# Hw_Sch.net
KiCad netlist of a schematic drawn in Altium Designer
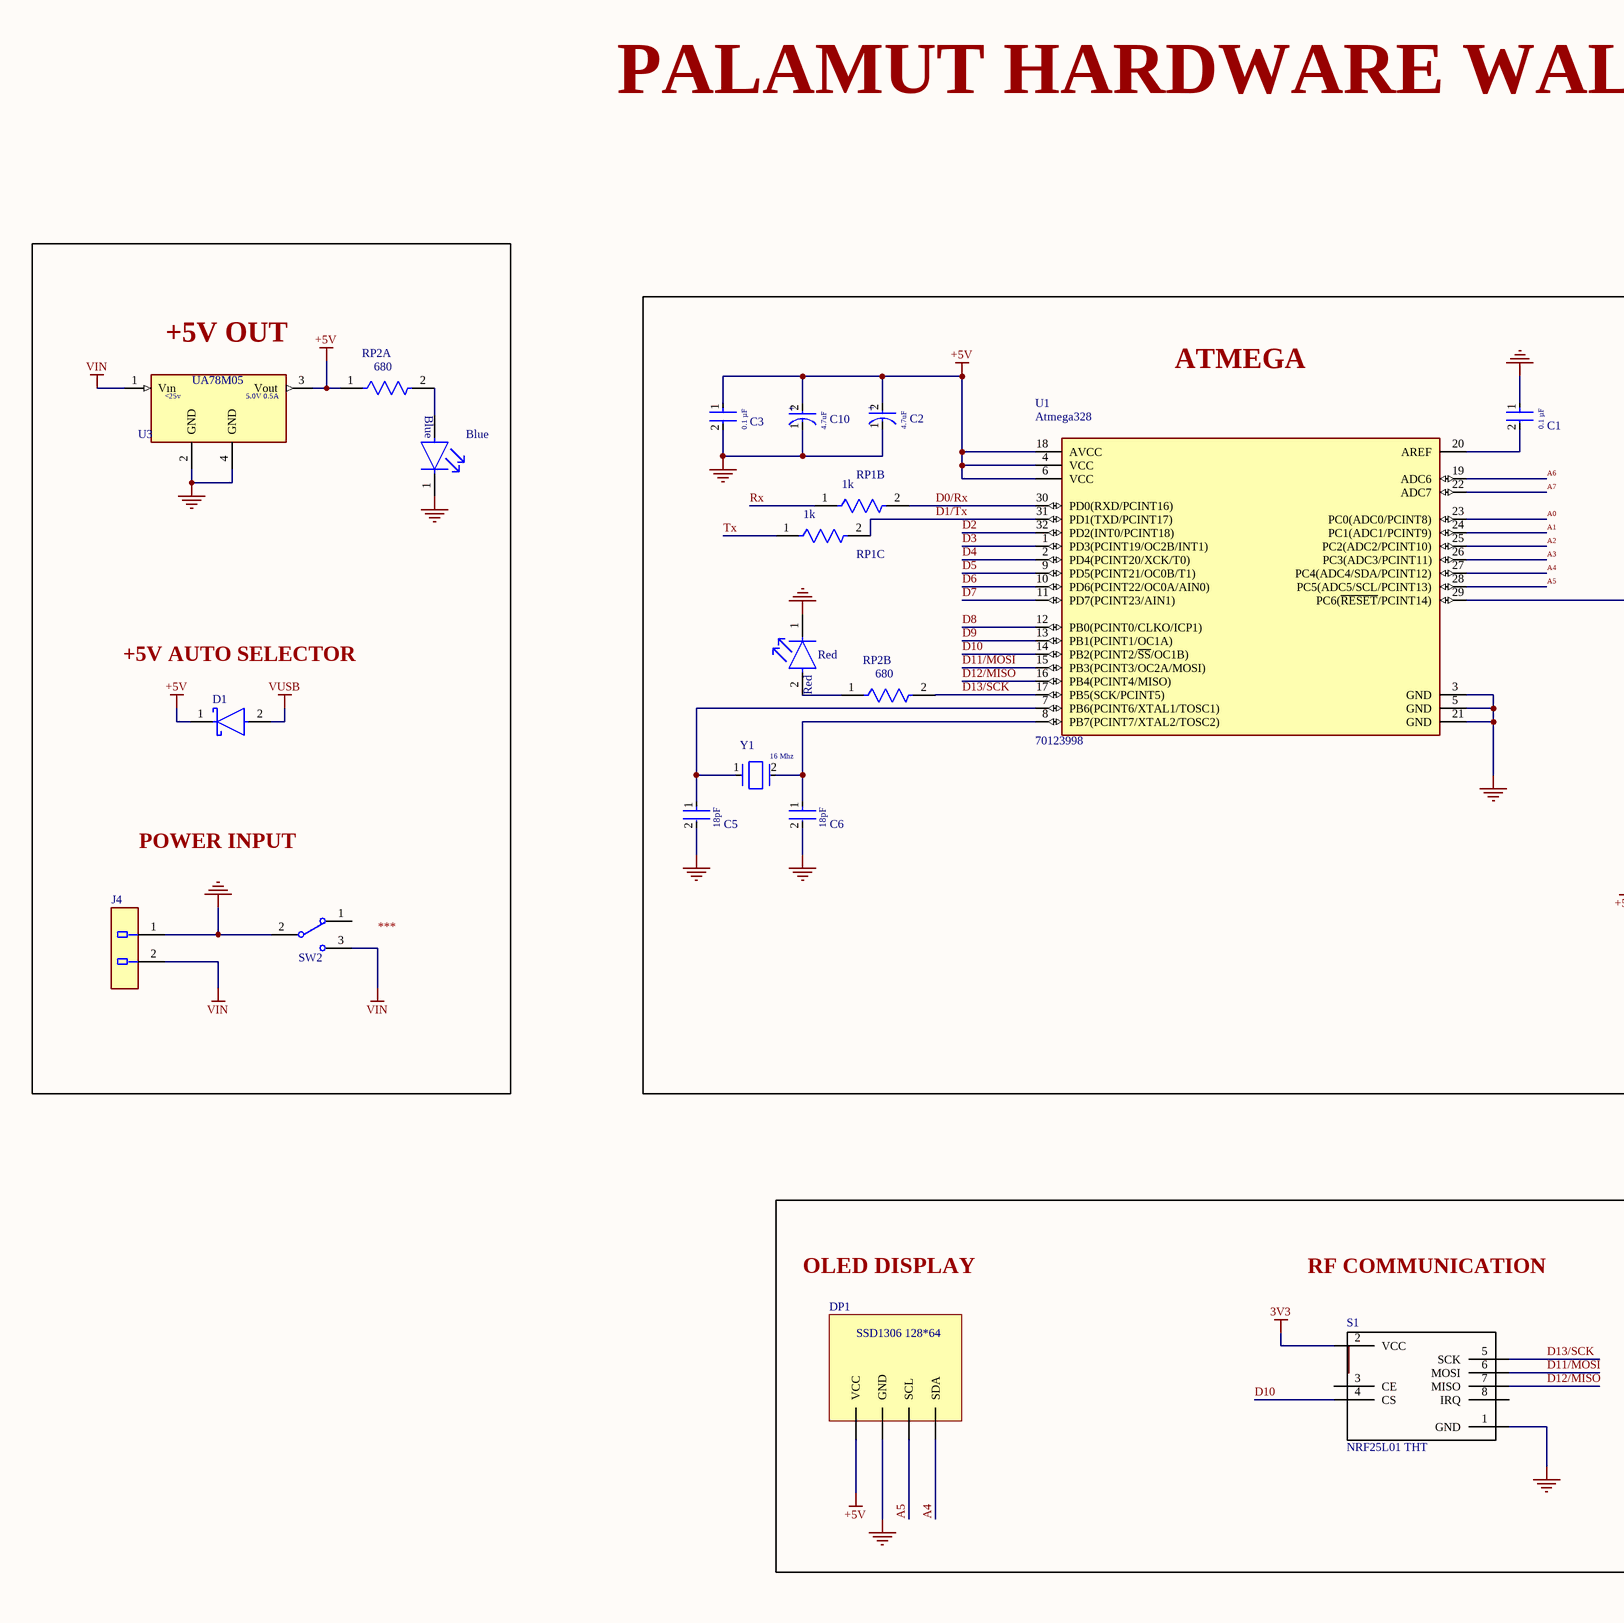
[diagram p0: Hw_Sch.SchDoc, left]
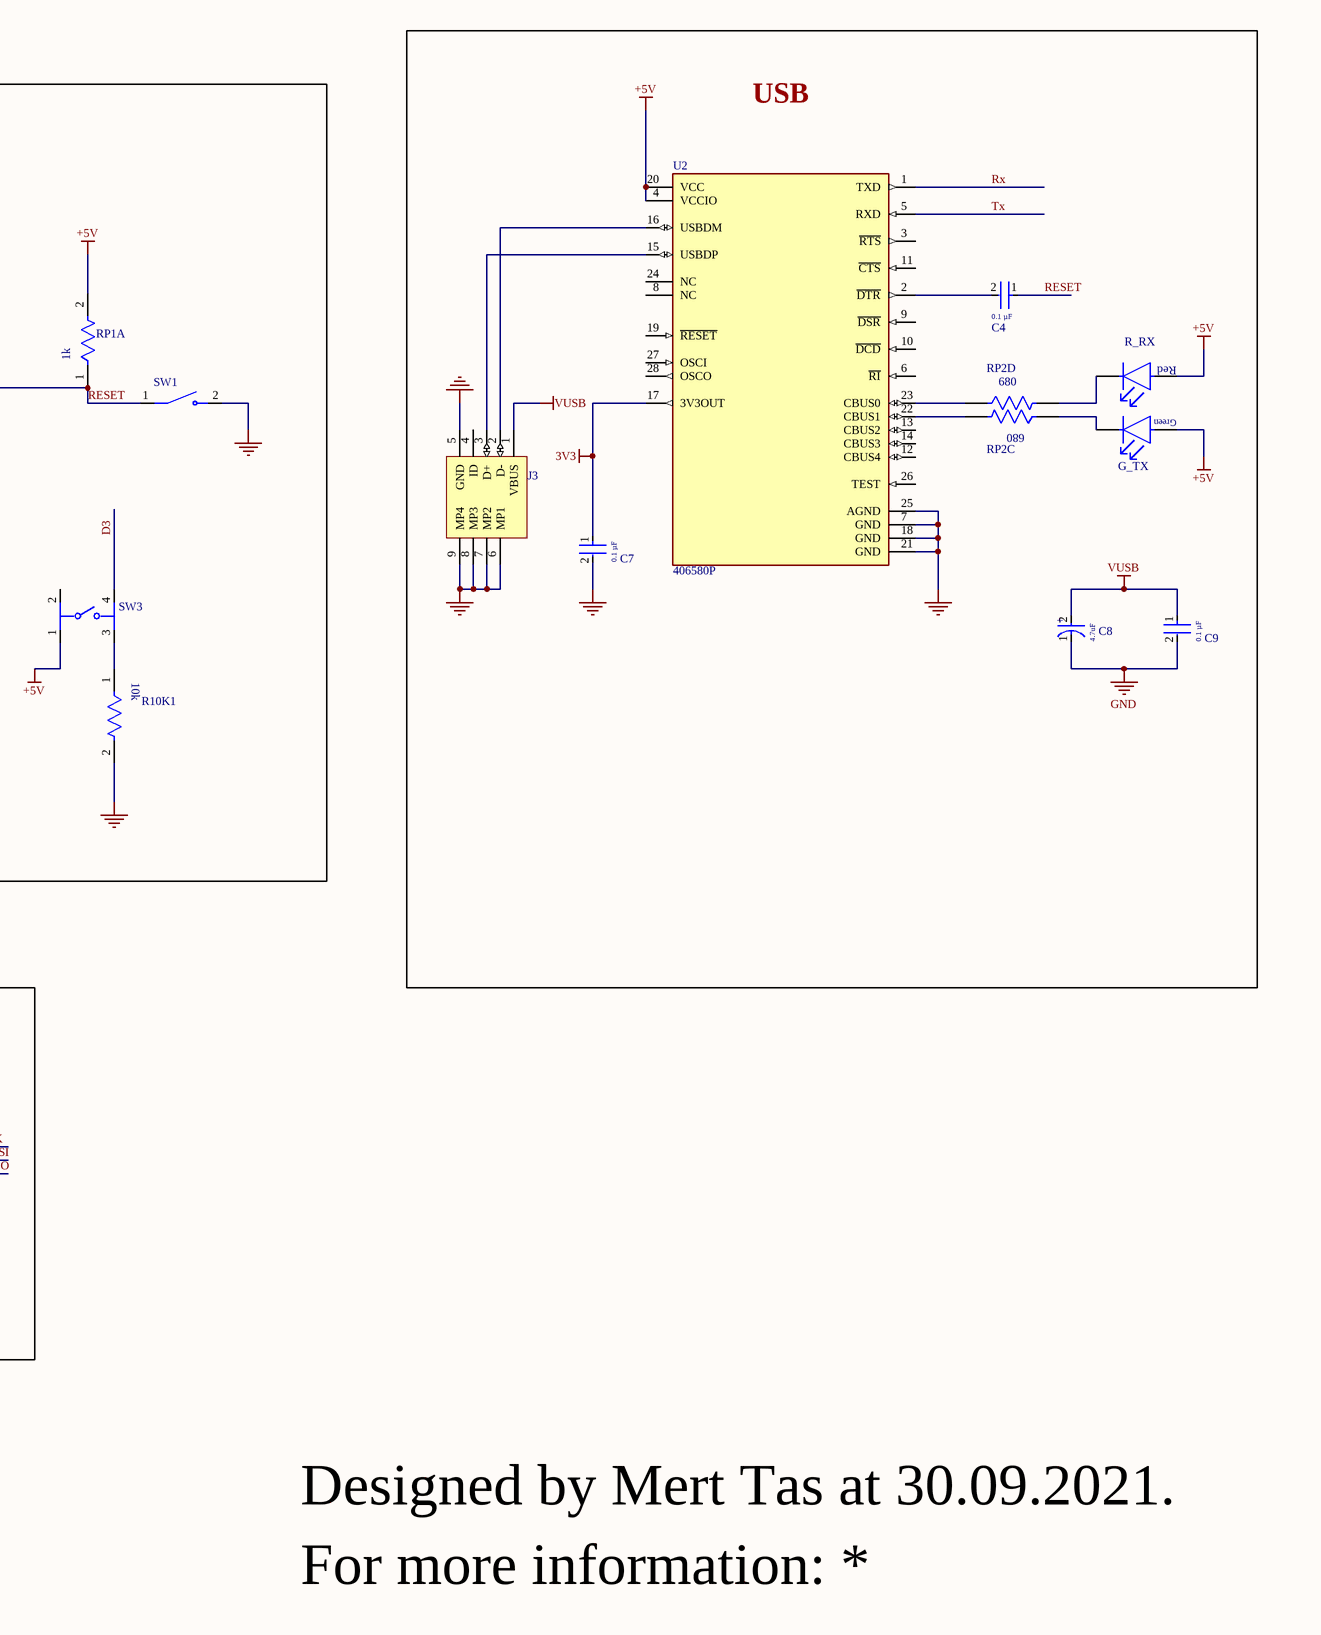
[diagram p1: Hw_Sch.SchDoc, right]

(export (version "E")
  (design (tool "Eeschema 10.0.6"))
  (components
    (comp (ref "Blue")
      (value "LTST-C170TBKT")
      (footprint "Lite-On_0_MFG")
      (libsource (lib "SCH_LED") (part "LTST-C170TBKT"))
    )
    (comp (ref "C1")
      (value "C0805C104K5RACTU")
      (footprint "KEMET_C0805C-DN_IPC_A")
      (libsource (lib "SCH_CAP") (part "C0805C104K5RACTU"))
    )
    (comp (ref "C2")
      (value "T491A475K010AT")
      (footprint "Kemet_T491A475K010AT_0")
      (libsource (lib "SCH_CAP") (part "T491A475K010AT"))
    )
    (comp (ref "C3")
      (value "C0805C104K5RACTU")
      (footprint "KEMET_C0805C-DN_IPC_A")
      (libsource (lib "SCH_CAP") (part "C0805C104K5RACTU"))
    )
    (comp (ref "C4")
      (value "C0805C104K5RACTU")
      (footprint "KEMET_C0805C-DN_IPC_A")
      (libsource (lib "SCH_CAP") (part "C0805C104K5RACTU"))
    )
    (comp (ref "C5")
      (value "C0805C180J5GACTU")
      (footprint "KEMET_C0805C-DN_IPC_A - duplicate")
      (libsource (lib "SCH_CAP") (part "C0805C180J5GACTU"))
    )
    (comp (ref "C6")
      (value "C0805C180J5GACTU")
      (footprint "KEMET_C0805C-DN_IPC_A - duplicate")
      (libsource (lib "SCH_CAP") (part "C0805C180J5GACTU"))
    )
    (comp (ref "C7")
      (value "C0805C104K5RACTU")
      (footprint "KEMET_C0805C-DN_IPC_A")
      (libsource (lib "SCH_CAP") (part "C0805C104K5RACTU"))
    )
    (comp (ref "C8")
      (value "T491A475K010AT")
      (footprint "Kemet_T491A475K010AT_0")
      (libsource (lib "SCH_CAP") (part "T491A475K010AT"))
    )
    (comp (ref "C9")
      (value "C0805C104K5RACTU")
      (footprint "KEMET_C0805C-DN_IPC_A")
      (libsource (lib "SCH_CAP") (part "C0805C104K5RACTU"))
    )
    (comp (ref "C10")
      (value "T491A475K010AT")
      (footprint "Kemet_T491A475K010AT_0")
      (libsource (lib "SCH_CAP") (part "T491A475K010AT"))
    )
    (comp (ref "D1")
      (value "MBR0520LT1G")
      (footprint "On_Semiconductor_425-04_IPC_A")
      (libsource (lib "SCH_DIOS") (part "MBR0520LT1G"))
    )
    (comp (ref "DP1")
      (value "SSD1306 0.96 inch")
      (footprint "SSD1306 128*64")
      (libsource (lib "SCH_LCD") (part "SSD1306 0.96 inch"))
    )
    (comp (ref "G_TX")
      (value "APHCM2012CGCK-F01")
      (footprint "Kingbright_0_MFG")
      (libsource (lib "SCH_LED") (part "APHCM2012CGCK-F01"))
    )
    (comp (ref "J3")
      (value "67503-1020")
      (footprint "MOLX-67503-1020_V")
      (description "USB, MINI, SMD, RA KME04-USBMU03A01")
      (fields (field (name "MANUFACTURER") "Molex"))
      (libsource (lib "SCH_CON") (part "67503-1020"))
    )
    (comp (ref "J4")
      (value "S2B-PH-K-S_LF_SN")
      (footprint "JST_S2B-PH-K-S_LF_SN_0")
      (libsource (lib "SCH_CON") (part "S2B-PH-K-S_LF_SN"))
    )
    (comp (ref "R10K1")
      (value "MCT0603MD1002DP500")
      (footprint "Vishay_MCT0603_IPC_A")
      (libsource (lib "SCH_RES") (part "MCT0603MD1002DP500"))
    )
    (comp (ref "Red")
      (value "APT2012SRCPRV")
      (footprint "Kingbright_APT2012SRCPRV_0")
      (libsource (lib "") (part "APT2012SRCPRV_1"))
    )
    (comp (ref "RP1A")
      (value "RC0603FR-071KL")
      (footprint "Yageo_RC0603_IPC_A - duplicate")
      (libsource (lib "SCH_RES") (part "RC0603FR-071KL"))
    )
    (comp (ref "RP1B")
      (value "RC0603FR-071KL")
      (footprint "Yageo_RC0603_IPC_A - duplicate")
      (libsource (lib "SCH_RES") (part "RC0603FR-071KL"))
    )
    (comp (ref "RP1C")
      (value "RC0603FR-071KL")
      (footprint "Yageo_RC0603_IPC_A - duplicate")
      (libsource (lib "SCH_RES") (part "RC0603FR-071KL"))
    )
    (comp (ref "RP2A")
      (value "RC0603FR-07680RL")
      (footprint "Yageo_RC0603_IPC_A")
      (libsource (lib "") (part "RC0603FR-07680RL_1"))
    )
    (comp (ref "RP2B")
      (value "RC0603FR-07680RL")
      (footprint "Yageo_RC0603_IPC_A")
      (libsource (lib "") (part "RC0603FR-07680RL_1"))
    )
    (comp (ref "RP2C")
      (value "RC0603FR-07680RL")
      (footprint "Yageo_RC0603_IPC_A")
      (libsource (lib "SCH_RES") (part "RC0603FR-07680RL"))
    )
    (comp (ref "RP2D")
      (value "RC0603FR-07680RL")
      (footprint "Yageo_RC0603_IPC_A")
      (libsource (lib "SCH_RES") (part "RC0603FR-07680RL"))
    )
    (comp (ref "R_RX")
      (value "APT2012SRCPRV")
      (footprint "Kingbright_APT2012SRCPRV_0")
      (libsource (lib "SCH_LED") (part "APT2012SRCPRV"))
    )
    (comp (ref "S1")
      (value "NRF25L01 THT")
      (footprint "NRF25L01 THT")
      (libsource (lib "SCH_RF") (part "NRF25L01 THT"))
    )
    (comp (ref "SW1")
      (value "B3U-1000P")
      (footprint "Omron_0_MFG")
      (description "Tactile Switch SPST-NO Top Actuated Surface Mount")
      (fields (field (name "MF") "Omron") (field (name "DIGI-KEY_PART_NUMBER") "SW1020CT-ND"))
      (libsource (lib "SCH_SW") (part "B3U-1000P"))
    )
    (comp (ref "SW2")
      (value "EG1218")
      (footprint "ESWI-EG1218_V")
      (description "Slide Switch, 500 V, -20 to 70 degC, 3-Pin THD, RoHS")
      (libsource (lib "SCH_SW") (part "EG1218"))
    )
    (comp (ref "SW3")
      (value "B3SL-1002P")
      (footprint "Omron_B3SL-1022P_0")
      (libsource (lib "SCH_SW") (part "B3SL-1002P"))
    )
    (comp (ref "U1")
      (value "ATMEGA168-20AU")
      (footprint "Microchip_32A_IPC_A")
      (fields (field (name "SUPPLIER PART NUMBER 1") "70123998"))
      (libsource (lib "SCH_IC") (part "ATMEGA168-20AU"))
    )
    (comp (ref "U2")
      (value "FT232RL-REEL")
      (footprint "FTDI_SSOP-28_IPC_A")
      (fields (field (name "SUPPLIER PART NUMBER 1") "406580P"))
      (libsource (lib "SCH_IC") (part "FT232RL-REEL"))
    )
    (comp (ref "U3")
      (value "UA78M05CDCYR")
      (footprint "Texas_Instruments_DCY0004A_IPC_A")
      (libsource (lib "SCH_IC") (part "UA78M05CDCYR"))
    )
    (comp (ref "Y1")
      (value "Crys_CTS_ATS16B_eec")
      (footprint "CTS_ATS16B_0")
      (description "CRYSTAL 16.0000MHZ 18PF T/H")
      (fields (field (name "PART NUMBER") "ATS16B") (field (name "MANUFACTURER") "CTS"))
      (libsource (lib "SCH_CRYSTAL") (part "Crys_CTS_ATS16B_eec"))
    )
  )
  (nets
    (net (code "1") (name "+5V") (class "Default")
      (node (ref "C10") (pin "2") (pinfunction "A_2") (pintype "passive"))
      (node (ref "C2") (pin "2") (pinfunction "A_2") (pintype "passive"))
      (node (ref "C3") (pin "1") (pinfunction "1_1") (pintype "passive"))
      (node (ref "D1") (pin "1") (pinfunction "C_1") (pintype "passive"))
      (node (ref "DP1") (pin "1") (pinfunction "VCC_1") (pintype "passive"))
      (node (ref "G_TX") (pin "2") (pinfunction "A_2") (pintype "passive"))
      (node (ref "RP1A") (pin "2") (pinfunction "2_2") (pintype "passive"))
      (node (ref "RP2A") (pin "1") (pinfunction "1_1") (pintype "passive"))
      (node (ref "R_RX") (pin "2") (pinfunction "A_2") (pintype "passive"))
      (node (ref "SW3") (pin "1") (pinfunction "1_1") (pintype "passive"))
      (node (ref "U1") (pin "18") (pinfunction "AVCC_18") (pintype "power_in"))
      (node (ref "U1") (pin "4") (pinfunction "VCC_4") (pintype "power_in"))
      (node (ref "U1") (pin "6") (pinfunction "VCC_6") (pintype "power_in"))
      (node (ref "U2") (pin "20") (pinfunction "VCC_20") (pintype "power_in"))
      (node (ref "U2") (pin "4") (pinfunction "VCCIO_4") (pintype "power_in"))
      (node (ref "U3") (pin "3") (pinfunction "Vout_3") (pintype "output"))
    )
    (net (code "2") (name "/A0") (class "Default")
      (node (ref "U1") (pin "23") (pinfunction "PC0(ADC0/PCINT8)_23") (pintype "bidirectional"))
    )
    (net (code "3") (name "/A1") (class "Default")
      (node (ref "U1") (pin "24") (pinfunction "PC1(ADC1/PCINT9)_24") (pintype "bidirectional"))
    )
    (net (code "4") (name "/A2") (class "Default")
      (node (ref "U1") (pin "25") (pinfunction "PC2(ADC2/PCINT10)_25") (pintype "bidirectional"))
    )
    (net (code "5") (name "/A3") (class "Default")
      (node (ref "U1") (pin "26") (pinfunction "PC3(ADC3/PCINT11)_26") (pintype "bidirectional"))
    )
    (net (code "6") (name "/A4") (class "Default")
      (node (ref "DP1") (pin "4") (pinfunction "SDA_4") (pintype "passive"))
      (node (ref "U1") (pin "27") (pinfunction "PC4(ADC4/SDA/PCINT12)_27") (pintype "bidirectional"))
    )
    (net (code "7") (name "/A5") (class "Default")
      (node (ref "DP1") (pin "3") (pinfunction "SCL_3") (pintype "passive"))
      (node (ref "U1") (pin "28") (pinfunction "PC5(ADC5/SCL/PCINT13)_28") (pintype "bidirectional"))
    )
    (net (code "8") (name "/A6") (class "Default")
      (node (ref "U1") (pin "19") (pinfunction "ADC6_19") (pintype "bidirectional"))
    )
    (net (code "9") (name "/A7") (class "Default")
      (node (ref "U1") (pin "22") (pinfunction "ADC7_22") (pintype "bidirectional"))
    )
    (net (code "10") (name "/D0{slash}Rx") (class "Default")
      (node (ref "RP1B") (pin "2") (pinfunction "2_2") (pintype "passive"))
      (node (ref "U1") (pin "30") (pinfunction "PD0(RXD/PCINT16)_30") (pintype "bidirectional"))
    )
    (net (code "11") (name "/D1{slash}Tx") (class "Default")
      (node (ref "RP1C") (pin "2") (pinfunction "2_2") (pintype "passive"))
      (node (ref "U1") (pin "31") (pinfunction "PD1(TXD/PCINT17)_31") (pintype "bidirectional"))
    )
    (net (code "12") (name "/D2") (class "Default")
      (node (ref "U1") (pin "32") (pinfunction "PD2(INT0/PCINT18)_32") (pintype "bidirectional"))
    )
    (net (code "13") (name "/D3") (class "Default")
      (node (ref "SW3") (pin "4") (pinfunction "4_4") (pintype "passive"))
      (node (ref "U1") (pin "1") (pinfunction "PD3(PCINT19/OC2B/INT1)_1") (pintype "bidirectional"))
    )
    (net (code "14") (name "/D4") (class "Default")
      (node (ref "U1") (pin "2") (pinfunction "PD4(PCINT20/XCK/T0)_2") (pintype "bidirectional"))
    )
    (net (code "15") (name "/D5") (class "Default")
      (node (ref "U1") (pin "9") (pinfunction "PD5(PCINT21/OC0B/T1)_9") (pintype "bidirectional"))
    )
    (net (code "16") (name "/D6") (class "Default")
      (node (ref "U1") (pin "10") (pinfunction "PD6(PCINT22/OC0A/AIN0)_10") (pintype "bidirectional"))
    )
    (net (code "17") (name "/D7") (class "Default")
      (node (ref "U1") (pin "11") (pinfunction "PD7(PCINT23/AIN1)_11") (pintype "bidirectional"))
    )
    (net (code "18") (name "/D8") (class "Default")
      (node (ref "U1") (pin "12") (pinfunction "PB0(PCINT0/CLKO/ICP1)_12") (pintype "bidirectional"))
    )
    (net (code "19") (name "/D9") (class "Default")
      (node (ref "U1") (pin "13") (pinfunction "PB1(PCINT1/OC1A)_13") (pintype "bidirectional"))
    )
    (net (code "20") (name "/D10") (class "Default")
      (node (ref "S1") (pin "4") (pinfunction "CS_4") (pintype "passive"))
      (node (ref "U1") (pin "14") (pinfunction "PB2(PCINT2/~{SS}/OC1B)_14") (pintype "bidirectional"))
    )
    (net (code "21") (name "/D11{slash}MOSI") (class "Default")
      (node (ref "S1") (pin "6") (pinfunction "MOSI_6") (pintype "passive"))
      (node (ref "U1") (pin "15") (pinfunction "PB3(PCINT3/OC2A/MOSI)_15") (pintype "bidirectional"))
    )
    (net (code "22") (name "/D12{slash}MISO") (class "Default")
      (node (ref "S1") (pin "7") (pinfunction "MISO_7") (pintype "passive"))
      (node (ref "U1") (pin "16") (pinfunction "PB4(PCINT4/MISO)_16") (pintype "bidirectional"))
    )
    (net (code "23") (name "/D13{slash}SCK") (class "Default")
      (node (ref "RP2B") (pin "2") (pinfunction "2_2") (pintype "passive"))
      (node (ref "S1") (pin "5") (pinfunction "SCK_5") (pintype "passive"))
      (node (ref "U1") (pin "17") (pinfunction "PB5(SCK/PCINT5)_17") (pintype "bidirectional"))
    )
    (net (code "24") (name "/RESET") (class "Default")
      (node (ref "C4") (pin "1") (pinfunction "1_1") (pintype "passive"))
      (node (ref "RP1A") (pin "1") (pinfunction "1_1") (pintype "passive"))
      (node (ref "SW1") (pin "1") (pinfunction "1_1") (pintype "passive"))
      (node (ref "U1") (pin "29") (pinfunction "PC6(~{RESET}/PCINT14)_29") (pintype "bidirectional"))
    )
    (net (code "25") (name "/Rx") (class "Default")
      (node (ref "RP1B") (pin "1") (pinfunction "1_1") (pintype "passive"))
      (node (ref "U2") (pin "1") (pinfunction "TXD_1") (pintype "output"))
    )
    (net (code "26") (name "/Tx") (class "Default")
      (node (ref "RP1C") (pin "1") (pinfunction "1_1") (pintype "passive"))
      (node (ref "U2") (pin "5") (pinfunction "RXD_5") (pintype "input"))
    )
    (net (code "27") (name "3V3") (class "Default")
      (node (ref "C7") (pin "1") (pinfunction "1_1") (pintype "passive"))
      (node (ref "S1") (pin "2") (pinfunction "VCC_2") (pintype "power_in"))
      (node (ref "U2") (pin "17") (pinfunction "3V3OUT_17") (pintype "output"))
    )
    (net (code "28") (name "GND") (class "Default")
      (node (ref "Blue") (pin "1") (pinfunction "C_1") (pintype "passive"))
      (node (ref "C1") (pin "1") (pinfunction "1_1") (pintype "passive"))
      (node (ref "C10") (pin "1") (pinfunction "C_1") (pintype "passive"))
      (node (ref "C2") (pin "1") (pinfunction "C_1") (pintype "passive"))
      (node (ref "C3") (pin "2") (pinfunction "2_2") (pintype "passive"))
      (node (ref "C5") (pin "2") (pinfunction "2_2") (pintype "passive"))
      (node (ref "C6") (pin "2") (pinfunction "2_2") (pintype "passive"))
      (node (ref "C7") (pin "2") (pinfunction "2_2") (pintype "passive"))
      (node (ref "C8") (pin "1") (pinfunction "C_1") (pintype "passive"))
      (node (ref "C9") (pin "2") (pinfunction "2_2") (pintype "passive"))
      (node (ref "DP1") (pin "2") (pinfunction "GND_2") (pintype "passive"))
      (node (ref "J3") (pin "5") (pinfunction "GND_5") (pintype "power_in"))
      (node (ref "J3") (pin "6") (pinfunction "MP1_6") (pintype "passive"))
      (node (ref "J3") (pin "7") (pinfunction "MP2_7") (pintype "passive"))
      (node (ref "J3") (pin "8") (pinfunction "MP3_8") (pintype "passive"))
      (node (ref "J3") (pin "9") (pinfunction "MP4_9") (pintype "passive"))
      (node (ref "J4") (pin "1") (pinfunction "1_1") (pintype "passive"))
      (node (ref "R10K1") (pin "2") (pinfunction "2_2") (pintype "passive"))
      (node (ref "Red") (pin "1") (pinfunction "C_1") (pintype "passive"))
      (node (ref "S1") (pin "1") (pinfunction "GND_1") (pintype "power_in"))
      (node (ref "SW1") (pin "2") (pinfunction "2_2") (pintype "passive"))
      (node (ref "SW2") (pin "2") (pinfunction "COM_2") (pintype "passive"))
      (node (ref "U1") (pin "21") (pinfunction "GND_21") (pintype "power_in"))
      (node (ref "U1") (pin "3") (pinfunction "GND_3") (pintype "power_in"))
      (node (ref "U1") (pin "5") (pinfunction "GND_5") (pintype "power_in"))
      (node (ref "U2") (pin "18") (pinfunction "GND_18") (pintype "power_in"))
      (node (ref "U2") (pin "21") (pinfunction "GND_21") (pintype "power_in"))
      (node (ref "U2") (pin "25") (pinfunction "AGND_25") (pintype "power_in"))
      (node (ref "U2") (pin "7") (pinfunction "GND_7") (pintype "power_in"))
      (node (ref "U3") (pin "2") (pinfunction "GND_2") (pintype "power_in"))
      (node (ref "U3") (pin "4") (pinfunction "GND_4") (pintype "power_in"))
    )
    (net (code "29") (name "Net-(Blue-A)") (class "Default")
      (node (ref "Blue") (pin "2") (pinfunction "A_2") (pintype "passive"))
      (node (ref "RP2A") (pin "2") (pinfunction "2_2") (pintype "passive"))
    )
    (net (code "30") (name "Net-(G_TX-C)") (class "Default")
      (node (ref "G_TX") (pin "1") (pinfunction "C_1") (pintype "passive"))
      (node (ref "RP2C") (pin "1") (pinfunction "1_1") (pintype "passive"))
    )
    (net (code "31") (name "Net-(J3-D+)") (class "Default")
      (node (ref "J3") (pin "3") (pinfunction "D+_3") (pintype "bidirectional"))
      (node (ref "U2") (pin "15") (pinfunction "USBDP_15") (pintype "bidirectional"))
    )
    (net (code "32") (name "Net-(J3-D-)") (class "Default")
      (node (ref "J3") (pin "2") (pinfunction "D-_2") (pintype "bidirectional"))
      (node (ref "U2") (pin "16") (pinfunction "USBDM_16") (pintype "bidirectional"))
    )
    (net (code "33") (name "Net-(R10K1-Pad1)") (class "Default")
      (node (ref "R10K1") (pin "1") (pinfunction "1_1") (pintype "passive"))
      (node (ref "SW3") (pin "3") (pinfunction "3_3") (pintype "passive"))
    )
    (net (code "34") (name "Net-(R_RX-C)") (class "Default")
      (node (ref "RP2D") (pin "2") (pinfunction "2_2") (pintype "passive"))
      (node (ref "R_RX") (pin "1") (pinfunction "C_1") (pintype "passive"))
    )
    (net (code "35") (name "Net-(Red-A)") (class "Default")
      (node (ref "RP2B") (pin "1") (pinfunction "1_1") (pintype "passive"))
      (node (ref "Red") (pin "2") (pinfunction "A_2") (pintype "passive"))
    )
    (net (code "36") (name "Net-(U1-AREF)") (class "Default")
      (node (ref "C1") (pin "2") (pinfunction "2_2") (pintype "passive"))
      (node (ref "U1") (pin "20") (pinfunction "AREF_20") (pintype "passive"))
    )
    (net (code "37") (name "Net-(U1-PB6(PCINT6{slash}XTAL1{slash}TOSC1))") (class "Default")
      (node (ref "C5") (pin "1") (pinfunction "1_1") (pintype "passive"))
      (node (ref "U1") (pin "7") (pinfunction "PB6(PCINT6/XTAL1/TOSC1)_7") (pintype "bidirectional"))
      (node (ref "Y1") (pin "1") (pinfunction "1_1") (pintype "passive"))
    )
    (net (code "38") (name "Net-(U1-PB7(PCINT7{slash}XTAL2{slash}TOSC2))") (class "Default")
      (node (ref "C6") (pin "1") (pinfunction "1_1") (pintype "passive"))
      (node (ref "U1") (pin "8") (pinfunction "PB7(PCINT7/XTAL2/TOSC2)_8") (pintype "bidirectional"))
      (node (ref "Y1") (pin "2") (pinfunction "2_2") (pintype "passive"))
    )
    (net (code "39") (name "Net-(U2-CBUS0)") (class "Default")
      (node (ref "RP2D") (pin "1") (pinfunction "1_1") (pintype "passive"))
      (node (ref "U2") (pin "23") (pinfunction "CBUS0_23") (pintype "bidirectional"))
    )
    (net (code "40") (name "Net-(U2-CBUS1)") (class "Default")
      (node (ref "RP2C") (pin "2") (pinfunction "2_2") (pintype "passive"))
      (node (ref "U2") (pin "22") (pinfunction "CBUS1_22") (pintype "bidirectional"))
    )
    (net (code "41") (name "Net-(U2-~{DTR})") (class "Default")
      (node (ref "C4") (pin "2") (pinfunction "2_2") (pintype "passive"))
      (node (ref "U2") (pin "2") (pinfunction "~{DTR}_2") (pintype "output"))
    )
    (net (code "42") (name "VIN") (class "Default")
      (node (ref "J4") (pin "2") (pinfunction "2_2") (pintype "passive"))
      (node (ref "SW2") (pin "3") (pinfunction "3_3") (pintype "passive"))
      (node (ref "U3") (pin "1") (pinfunction "Vın_1") (pintype "input"))
    )
    (net (code "43") (name "VUSB") (class "Default")
      (node (ref "C8") (pin "2") (pinfunction "A_2") (pintype "passive"))
      (node (ref "C9") (pin "1") (pinfunction "1_1") (pintype "passive"))
      (node (ref "D1") (pin "2") (pinfunction "A_2") (pintype "passive"))
      (node (ref "J3") (pin "1") (pinfunction "VBUS_1") (pintype "power_in"))
    )
    (net (code "44") (name "unconnected-(J3-ID-Pad4)") (class "Default")
      (node (ref "J3") (pin "4") (pinfunction "ID_4") (pintype "passive"))
    )
    (net (code "45") (name "unconnected-(S1-CE-Pad3)") (class "Default")
      (node (ref "S1") (pin "3") (pinfunction "CE_3") (pintype "passive"))
    )
    (net (code "46") (name "unconnected-(S1-IRQ-Pad8)") (class "Default")
      (node (ref "S1") (pin "8") (pinfunction "IRQ_8") (pintype "passive"))
    )
    (net (code "47") (name "unconnected-(SW2-Pad1)") (class "Default")
      (node (ref "SW2") (pin "1") (pinfunction "1_1") (pintype "passive"))
    )
    (net (code "48") (name "unconnected-(SW3-Pad2)") (class "Default")
      (node (ref "SW3") (pin "2") (pinfunction "2_2") (pintype "passive"))
    )
    (net (code "49") (name "unconnected-(U2-CBUS2-Pad13)") (class "Default")
      (node (ref "U2") (pin "13") (pinfunction "CBUS2_13") (pintype "bidirectional"))
    )
    (net (code "50") (name "unconnected-(U2-CBUS3-Pad14)") (class "Default")
      (node (ref "U2") (pin "14") (pinfunction "CBUS3_14") (pintype "bidirectional"))
    )
    (net (code "51") (name "unconnected-(U2-CBUS4-Pad12)") (class "Default")
      (node (ref "U2") (pin "12") (pinfunction "CBUS4_12") (pintype "bidirectional"))
    )
    (net (code "52") (name "unconnected-(U2-NC-Pad8)") (class "Default")
      (node (ref "U2") (pin "8") (pinfunction "NC_8") (pintype "passive"))
    )
    (net (code "53") (name "unconnected-(U2-NC-Pad24)") (class "Default")
      (node (ref "U2") (pin "24") (pinfunction "NC_24") (pintype "passive"))
    )
    (net (code "54") (name "unconnected-(U2-OSCI-Pad27)") (class "Default")
      (node (ref "U2") (pin "27") (pinfunction "OSCI_27") (pintype "input"))
    )
    (net (code "55") (name "unconnected-(U2-OSCO-Pad28)") (class "Default")
      (node (ref "U2") (pin "28") (pinfunction "OSCO_28") (pintype "output"))
    )
    (net (code "56") (name "unconnected-(U2-TEST-Pad26)") (class "Default")
      (node (ref "U2") (pin "26") (pinfunction "TEST_26") (pintype "input"))
    )
    (net (code "57") (name "unconnected-(U2-~{CTS}-Pad11)") (class "Default")
      (node (ref "U2") (pin "11") (pinfunction "~{CTS}_11") (pintype "input"))
    )
    (net (code "58") (name "unconnected-(U2-~{DCD}-Pad10)") (class "Default")
      (node (ref "U2") (pin "10") (pinfunction "~{DCD}_10") (pintype "input"))
    )
    (net (code "59") (name "unconnected-(U2-~{DSR}-Pad9)") (class "Default")
      (node (ref "U2") (pin "9") (pinfunction "~{DSR}_9") (pintype "input"))
    )
    (net (code "60") (name "unconnected-(U2-~{RESET}-Pad19)") (class "Default")
      (node (ref "U2") (pin "19") (pinfunction "~{RESET}_19") (pintype "input"))
    )
    (net (code "61") (name "unconnected-(U2-~{RI}-Pad6)") (class "Default")
      (node (ref "U2") (pin "6") (pinfunction "~{RI}_6") (pintype "input"))
    )
    (net (code "62") (name "unconnected-(U2-~{RTS}-Pad3)") (class "Default")
      (node (ref "U2") (pin "3") (pinfunction "~{RTS}_3") (pintype "output"))
    )
  )
)
